# 3_Phase_Controller_V0_1.net
KiCad netlist of a schematic drawn in EAGLE
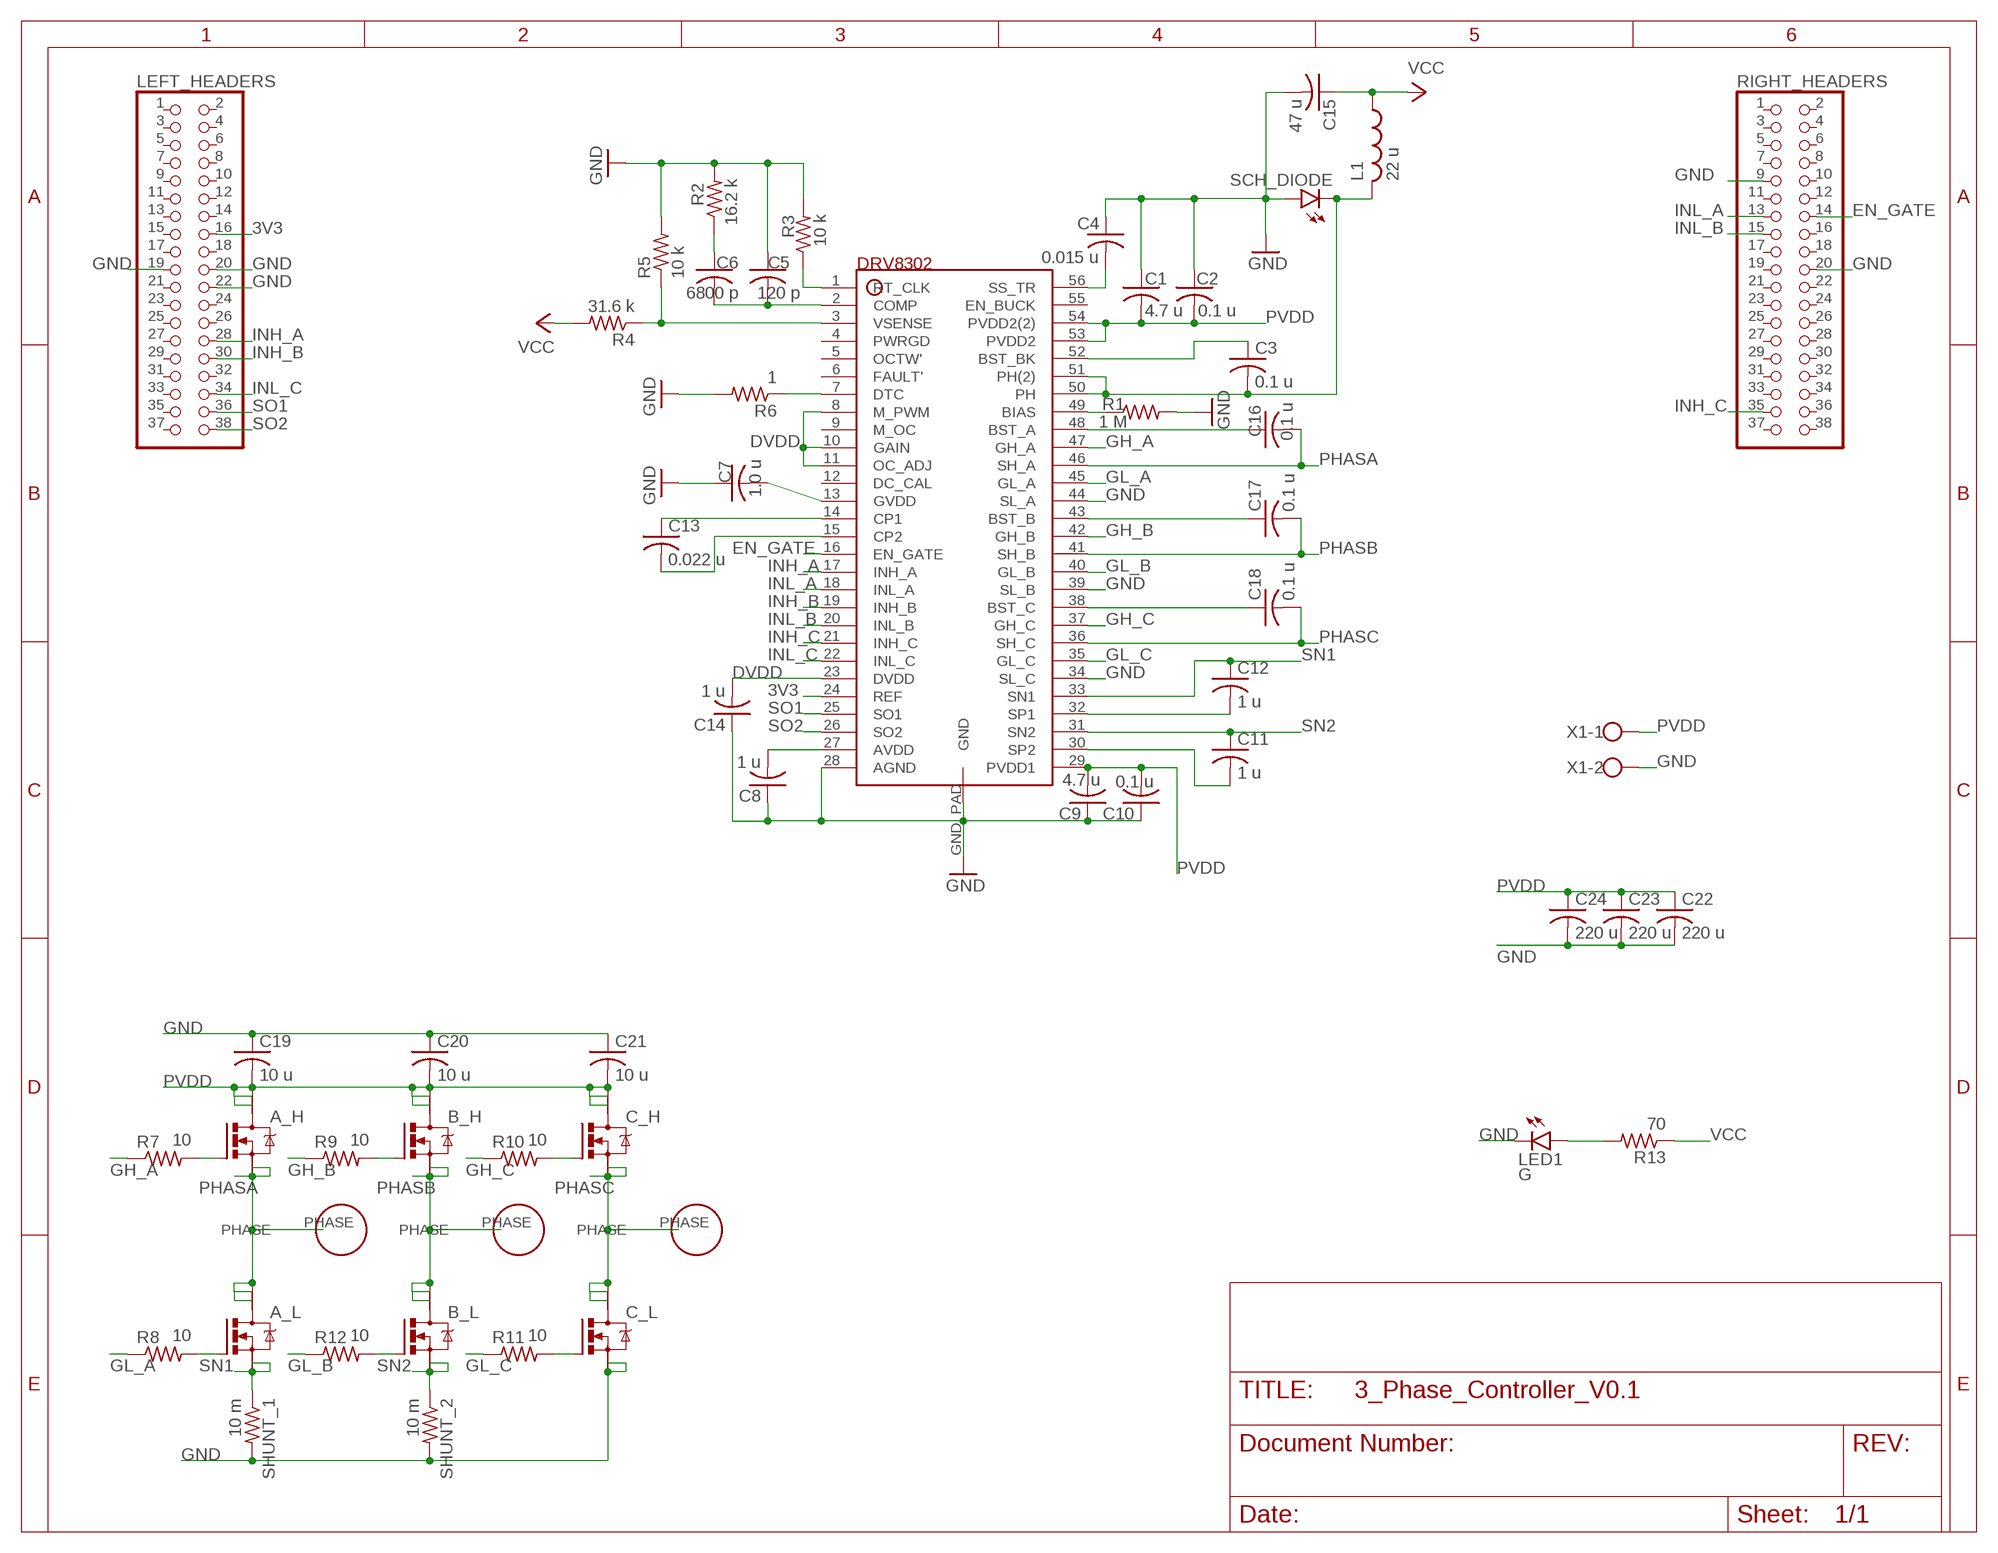
[diagram p0: schematic, sheet 1]

(export (version "E")
  (design (tool "Eeschema 10.0.6"))
  (components
    (comp (ref "A")
      (value "PHASE_HOLE")
      (footprint "eagle-import:HOLE")
      (libsource (lib "eagle-import") (part "PHASE_HOLE"))
    )
    (comp (ref "A_H")
      (value "N-MOSFET-SO8S")
      (footprint "eagle-import:SO-08")
      (libsource (lib "eagle-import") (part "N-MOSFET-SO8S"))
    )
    (comp (ref "A_L")
      (value "N-MOSFET-SO8S")
      (footprint "eagle-import:SO-08")
      (libsource (lib "eagle-import") (part "N-MOSFET-SO8S"))
    )
    (comp (ref "B")
      (value "PHASE_HOLE")
      (footprint "eagle-import:HOLE")
      (libsource (lib "eagle-import") (part "PHASE_HOLE"))
    )
    (comp (ref "B_H")
      (value "N-MOSFET-SO8S")
      (footprint "eagle-import:SO-08")
      (libsource (lib "eagle-import") (part "N-MOSFET-SO8S"))
    )
    (comp (ref "B_L")
      (value "N-MOSFET-SO8S")
      (footprint "eagle-import:SO-08")
      (libsource (lib "eagle-import") (part "N-MOSFET-SO8S"))
    )
    (comp (ref "C")
      (value "PHASE_HOLE")
      (footprint "eagle-import:HOLE")
      (libsource (lib "eagle-import") (part "PHASE_HOLE"))
    )
    (comp (ref "C1")
      (value "4.7 u")
      (footprint "eagle-import:C0805")
      (libsource (lib "eagle-import") (part "C-USC0805"))
    )
    (comp (ref "C2")
      (value "0.1 u")
      (footprint "eagle-import:C0805")
      (libsource (lib "eagle-import") (part "C-USC0805"))
    )
    (comp (ref "C3")
      (value "0.1 u")
      (footprint "eagle-import:C0805")
      (libsource (lib "eagle-import") (part "C-USC0805"))
    )
    (comp (ref "C4")
      (value "0.015 u")
      (footprint "eagle-import:C0805")
      (libsource (lib "eagle-import") (part "C-USC0805"))
    )
    (comp (ref "C5")
      (value "120 p")
      (footprint "eagle-import:C0805")
      (libsource (lib "eagle-import") (part "C-USC0805"))
    )
    (comp (ref "C6")
      (value "6800 p")
      (footprint "eagle-import:C0805")
      (libsource (lib "eagle-import") (part "C-USC0805"))
    )
    (comp (ref "C7")
      (value "1.0 u")
      (footprint "eagle-import:C0805")
      (libsource (lib "eagle-import") (part "C-USC0805"))
    )
    (comp (ref "C8")
      (value "1 u")
      (footprint "eagle-import:C0805")
      (libsource (lib "eagle-import") (part "C-USC0805"))
    )
    (comp (ref "C9")
      (value "4.7 u")
      (footprint "eagle-import:C0805")
      (libsource (lib "eagle-import") (part "C-USC0805"))
    )
    (comp (ref "C10")
      (value "0.1 u")
      (footprint "eagle-import:C0805")
      (libsource (lib "eagle-import") (part "C-USC0805"))
    )
    (comp (ref "C11")
      (value "1 u")
      (footprint "eagle-import:C0805")
      (libsource (lib "eagle-import") (part "C-USC0805"))
    )
    (comp (ref "C12")
      (value "1 u")
      (footprint "eagle-import:C0805")
      (libsource (lib "eagle-import") (part "C-USC0805"))
    )
    (comp (ref "C13")
      (value "0.022 u")
      (footprint "eagle-import:C0805")
      (libsource (lib "eagle-import") (part "C-USC0805"))
    )
    (comp (ref "C14")
      (value "1 u")
      (footprint "eagle-import:C0805")
      (libsource (lib "eagle-import") (part "C-USC0805"))
    )
    (comp (ref "C15")
      (value "47 u")
      (footprint "eagle-import:C025-024X044")
      (libsource (lib "eagle-import") (part "C-US025-024X044"))
    )
    (comp (ref "C16")
      (value "0.1 u")
      (footprint "eagle-import:C0805")
      (libsource (lib "eagle-import") (part "C-USC0805"))
    )
    (comp (ref "C17")
      (value "0.1 u")
      (footprint "eagle-import:C0805")
      (libsource (lib "eagle-import") (part "C-USC0805"))
    )
    (comp (ref "C18")
      (value "0.1 u")
      (footprint "eagle-import:C0805")
      (libsource (lib "eagle-import") (part "C-USC0805"))
    )
    (comp (ref "C19")
      (value "10 u")
      (footprint "eagle-import:C1206")
      (libsource (lib "eagle-import") (part "C-USC1206"))
    )
    (comp (ref "C20")
      (value "10 u")
      (footprint "eagle-import:C1206")
      (libsource (lib "eagle-import") (part "C-USC1206"))
    )
    (comp (ref "C21")
      (value "10 u")
      (footprint "eagle-import:C1206")
      (libsource (lib "eagle-import") (part "C-USC1206"))
    )
    (comp (ref "C22")
      (value "220 u")
      (footprint "eagle-import:C050-045X075")
      (libsource (lib "eagle-import") (part "C-US050-045X075"))
    )
    (comp (ref "C23")
      (value "220 u")
      (footprint "eagle-import:C050-045X075")
      (libsource (lib "eagle-import") (part "C-US050-045X075"))
    )
    (comp (ref "C24")
      (value "220 u")
      (footprint "eagle-import:C050-045X075")
      (libsource (lib "eagle-import") (part "C-US050-045X075"))
    )
    (comp (ref "C_H")
      (value "N-MOSFET-SO8S")
      (footprint "eagle-import:SO-08")
      (libsource (lib "eagle-import") (part "N-MOSFET-SO8S"))
    )
    (comp (ref "C_L")
      (value "N-MOSFET-SO8S")
      (footprint "eagle-import:SO-08")
      (libsource (lib "eagle-import") (part "N-MOSFET-SO8S"))
    )
    (comp (ref "DRV8302")
      (value "DRV8302HTSSOP_56")
      (footprint "eagle-import:HTSSOP56DFD")
      (libsource (lib "eagle-import") (part "DRV8302HTSSOP_56"))
    )
    (comp (ref "L1")
      (value "22 u")
      (footprint "eagle-import:L3225M")
      (libsource (lib "eagle-import") (part "L-USL3225M"))
    )
    (comp (ref "LED1")
      (value "G")
      (footprint "eagle-import:SML0805")
      (libsource (lib "eagle-import") (part "LEDSML0805"))
    )
    (comp (ref "LEFT_HEADERS")
      (value "F_PINH 2X19")
      (footprint "eagle-import:2X19")
      (libsource (lib "eagle-import") (part "PINHD-2X19"))
    )
    (comp (ref "R1")
      (value "1 M")
      (footprint "eagle-import:R0805")
      (libsource (lib "eagle-import") (part "R-US_R0805"))
    )
    (comp (ref "R2")
      (value "16.2 k")
      (footprint "eagle-import:R0805")
      (libsource (lib "eagle-import") (part "R-US_R0805"))
    )
    (comp (ref "R3")
      (value "10 k")
      (footprint "eagle-import:R0805")
      (libsource (lib "eagle-import") (part "R-US_R0805"))
    )
    (comp (ref "R4")
      (value "31.6 k")
      (footprint "eagle-import:R0805")
      (libsource (lib "eagle-import") (part "R-US_R0805"))
    )
    (comp (ref "R5")
      (value "10 k")
      (footprint "eagle-import:R0805")
      (libsource (lib "eagle-import") (part "R-US_R0805"))
    )
    (comp (ref "R6")
      (value "1")
      (footprint "eagle-import:R0805")
      (libsource (lib "eagle-import") (part "R-US_R0805"))
    )
    (comp (ref "R7")
      (value "10")
      (footprint "eagle-import:R0805")
      (libsource (lib "eagle-import") (part "R-US_R0805"))
    )
    (comp (ref "R8")
      (value "10")
      (footprint "eagle-import:R0805")
      (libsource (lib "eagle-import") (part "R-US_R0805"))
    )
    (comp (ref "R9")
      (value "10")
      (footprint "eagle-import:R0805")
      (libsource (lib "eagle-import") (part "R-US_R0805"))
    )
    (comp (ref "R10")
      (value "10")
      (footprint "eagle-import:R0805")
      (libsource (lib "eagle-import") (part "R-US_R0805"))
    )
    (comp (ref "R11")
      (value "10")
      (footprint "eagle-import:R0805")
      (libsource (lib "eagle-import") (part "R-US_R0805"))
    )
    (comp (ref "R12")
      (value "10")
      (footprint "eagle-import:R0805")
      (libsource (lib "eagle-import") (part "R-US_R0805"))
    )
    (comp (ref "R13")
      (value "70")
      (footprint "eagle-import:R0805")
      (libsource (lib "eagle-import") (part "R-US_R0805"))
    )
    (comp (ref "RIGHT_HEADERS")
      (value "F_PINH 2X19")
      (footprint "eagle-import:2X19")
      (libsource (lib "eagle-import") (part "PINHD-2X19"))
    )
    (comp (ref "SCH_DIODE")
      (value "LEDCHIP-LED0805")
      (footprint "eagle-import:CHIP-LED0805")
      (libsource (lib "eagle-import") (part "LEDCHIP-LED0805"))
    )
    (comp (ref "SHUNT_1")
      (value "10 m")
      (footprint "eagle-import:R2512")
      (libsource (lib "eagle-import") (part "R-US_R2512"))
    )
    (comp (ref "SHUNT_2")
      (value "10 m")
      (footprint "eagle-import:R2512")
      (libsource (lib "eagle-import") (part "R-US_R2512"))
    )
    (comp (ref "X1")
      (value "W237-102")
      (footprint "eagle-import:W237-102")
      (fields (field (name "MPN") "237-102"))
      (libsource (lib "eagle-import") (part "W237-102"))
    )
  )
  (nets
    (net (code "1") (name "/3V3") (class "Default")
      (node (ref "DRV8302") (pin "24") (pinfunction "REF_24") (pintype "bidirectional"))
      (node (ref "LEFT_HEADERS") (pin "16") (pinfunction "16_16") (pintype "passive"))
    )
    (net (code "2") (name "/DVDD") (class "Default")
      (node (ref "C14") (pin "2") (pinfunction "2_2") (pintype "passive"))
      (node (ref "DRV8302") (pin "10") (pinfunction "GAIN_10") (pintype "bidirectional"))
      (node (ref "DRV8302") (pin "11") (pinfunction "OC_ADJ_11") (pintype "bidirectional"))
      (node (ref "DRV8302") (pin "23") (pinfunction "DVDD_23") (pintype "bidirectional"))
      (node (ref "DRV8302") (pin "8") (pinfunction "M_PWM_8") (pintype "bidirectional"))
    )
    (net (code "3") (name "/EN_GATE") (class "Default")
      (node (ref "DRV8302") (pin "16") (pinfunction "EN_GATE_16") (pintype "bidirectional"))
      (node (ref "RIGHT_HEADERS") (pin "14") (pinfunction "14_14") (pintype "passive"))
    )
    (net (code "4") (name "/GH_A") (class "Default")
      (node (ref "DRV8302") (pin "47") (pinfunction "GH_A_47") (pintype "bidirectional"))
      (node (ref "R7") (pin "1") (pinfunction "1_1") (pintype "passive"))
    )
    (net (code "5") (name "/GH_B") (class "Default")
      (node (ref "DRV8302") (pin "42") (pinfunction "GH_B_42") (pintype "bidirectional"))
      (node (ref "R9") (pin "1") (pinfunction "1_1") (pintype "passive"))
    )
    (net (code "6") (name "/GH_C") (class "Default")
      (node (ref "DRV8302") (pin "37") (pinfunction "GH_C_37") (pintype "bidirectional"))
      (node (ref "R10") (pin "1") (pinfunction "1_1") (pintype "passive"))
    )
    (net (code "7") (name "/GL_A") (class "Default")
      (node (ref "DRV8302") (pin "45") (pinfunction "GL_A_45") (pintype "bidirectional"))
      (node (ref "R8") (pin "1") (pinfunction "1_1") (pintype "passive"))
    )
    (net (code "8") (name "/GL_B") (class "Default")
      (node (ref "DRV8302") (pin "40") (pinfunction "GL_B_40") (pintype "bidirectional"))
      (node (ref "R12") (pin "1") (pinfunction "1_1") (pintype "passive"))
    )
    (net (code "9") (name "/GL_C") (class "Default")
      (node (ref "DRV8302") (pin "35") (pinfunction "GL_C_35") (pintype "bidirectional"))
      (node (ref "R11") (pin "1") (pinfunction "1_1") (pintype "passive"))
    )
    (net (code "10") (name "/INH_A") (class "Default")
      (node (ref "DRV8302") (pin "17") (pinfunction "INH_A_17") (pintype "bidirectional"))
      (node (ref "LEFT_HEADERS") (pin "28") (pinfunction "28_28") (pintype "passive"))
    )
    (net (code "11") (name "/INH_B") (class "Default")
      (node (ref "DRV8302") (pin "19") (pinfunction "INH_B_19") (pintype "bidirectional"))
      (node (ref "LEFT_HEADERS") (pin "30") (pinfunction "30_30") (pintype "passive"))
    )
    (net (code "12") (name "/INH_C") (class "Default")
      (node (ref "DRV8302") (pin "21") (pinfunction "INH_C_21") (pintype "bidirectional"))
      (node (ref "RIGHT_HEADERS") (pin "35") (pinfunction "35_35") (pintype "passive"))
    )
    (net (code "13") (name "/INL_A") (class "Default")
      (node (ref "DRV8302") (pin "18") (pinfunction "INL_A_18") (pintype "bidirectional"))
      (node (ref "RIGHT_HEADERS") (pin "13") (pinfunction "13_13") (pintype "passive"))
    )
    (net (code "14") (name "/INL_B") (class "Default")
      (node (ref "DRV8302") (pin "20") (pinfunction "INL_B_20") (pintype "bidirectional"))
      (node (ref "RIGHT_HEADERS") (pin "15") (pinfunction "15_15") (pintype "passive"))
    )
    (net (code "15") (name "/INL_C") (class "Default")
      (node (ref "DRV8302") (pin "22") (pinfunction "INL_C_22") (pintype "bidirectional"))
      (node (ref "LEFT_HEADERS") (pin "34") (pinfunction "34_34") (pintype "passive"))
    )
    (net (code "16") (name "/PHASA") (class "Default")
      (node (ref "A") (pin "PHASE") (pinfunction "PHASE_PHASE") (pintype "bidirectional"))
      (node (ref "A_H") (pin "1") (pinfunction "S_1") (pintype "passive"))
      (node (ref "A_H") (pin "2") (pinfunction "S_2") (pintype "passive"))
      (node (ref "A_L") (pin "5") (pinfunction "D_5") (pintype "passive"))
      (node (ref "A_L") (pin "6") (pinfunction "D_6") (pintype "passive"))
      (node (ref "A_L") (pin "7") (pinfunction "D_7") (pintype "passive"))
      (node (ref "C16") (pin "2") (pinfunction "2_2") (pintype "passive"))
      (node (ref "DRV8302") (pin "46") (pinfunction "SH_A_46") (pintype "bidirectional"))
    )
    (net (code "17") (name "/PHASB") (class "Default")
      (node (ref "B") (pin "PHASE") (pinfunction "PHASE_PHASE") (pintype "bidirectional"))
      (node (ref "B_H") (pin "1") (pinfunction "S_1") (pintype "passive"))
      (node (ref "B_H") (pin "2") (pinfunction "S_2") (pintype "passive"))
      (node (ref "B_L") (pin "5") (pinfunction "D_5") (pintype "passive"))
      (node (ref "B_L") (pin "6") (pinfunction "D_6") (pintype "passive"))
      (node (ref "B_L") (pin "7") (pinfunction "D_7") (pintype "passive"))
      (node (ref "C17") (pin "2") (pinfunction "2_2") (pintype "passive"))
      (node (ref "DRV8302") (pin "41") (pinfunction "SH_B_41") (pintype "bidirectional"))
    )
    (net (code "18") (name "/PHASC") (class "Default")
      (node (ref "C") (pin "PHASE") (pinfunction "PHASE_PHASE") (pintype "bidirectional"))
      (node (ref "C18") (pin "2") (pinfunction "2_2") (pintype "passive"))
      (node (ref "C_H") (pin "1") (pinfunction "S_1") (pintype "passive"))
      (node (ref "C_H") (pin "2") (pinfunction "S_2") (pintype "passive"))
      (node (ref "C_L") (pin "5") (pinfunction "D_5") (pintype "passive"))
      (node (ref "C_L") (pin "6") (pinfunction "D_6") (pintype "passive"))
      (node (ref "C_L") (pin "7") (pinfunction "D_7") (pintype "passive"))
      (node (ref "DRV8302") (pin "36") (pinfunction "SH_C_36") (pintype "bidirectional"))
    )
    (net (code "19") (name "/PVDD") (class "Default")
      (node (ref "A_H") (pin "5") (pinfunction "D_5") (pintype "passive"))
      (node (ref "A_H") (pin "6") (pinfunction "D_6") (pintype "passive"))
      (node (ref "A_H") (pin "7") (pinfunction "D_7") (pintype "passive"))
      (node (ref "B_H") (pin "5") (pinfunction "D_5") (pintype "passive"))
      (node (ref "B_H") (pin "6") (pinfunction "D_6") (pintype "passive"))
      (node (ref "B_H") (pin "7") (pinfunction "D_7") (pintype "passive"))
      (node (ref "C1") (pin "2") (pinfunction "2_2") (pintype "passive"))
      (node (ref "C10") (pin "2") (pinfunction "2_2") (pintype "passive"))
      (node (ref "C19") (pin "2") (pinfunction "2_2") (pintype "passive"))
      (node (ref "C2") (pin "2") (pinfunction "2_2") (pintype "passive"))
      (node (ref "C20") (pin "2") (pinfunction "2_2") (pintype "passive"))
      (node (ref "C21") (pin "2") (pinfunction "2_2") (pintype "passive"))
      (node (ref "C22") (pin "1") (pinfunction "1_1") (pintype "passive"))
      (node (ref "C23") (pin "1") (pinfunction "1_1") (pintype "passive"))
      (node (ref "C24") (pin "1") (pinfunction "1_1") (pintype "passive"))
      (node (ref "C9") (pin "2") (pinfunction "2_2") (pintype "passive"))
      (node (ref "C_H") (pin "5") (pinfunction "D_5") (pintype "passive"))
      (node (ref "C_H") (pin "6") (pinfunction "D_6") (pintype "passive"))
      (node (ref "C_H") (pin "7") (pinfunction "D_7") (pintype "passive"))
      (node (ref "DRV8302") (pin "29") (pinfunction "PVDD1_29") (pintype "bidirectional"))
      (node (ref "DRV8302") (pin "53") (pinfunction "PVDD2_53") (pintype "bidirectional"))
      (node (ref "DRV8302") (pin "54") (pinfunction "PVDD2(2)_54") (pintype "bidirectional"))
      (node (ref "X1") (pin "1") (pinfunction "KL_1") (pintype "passive"))
    )
    (net (code "20") (name "/SN1") (class "Default")
      (node (ref "A_L") (pin "1") (pinfunction "S_1") (pintype "passive"))
      (node (ref "A_L") (pin "2") (pinfunction "S_2") (pintype "passive"))
      (node (ref "C12") (pin "1") (pinfunction "1_1") (pintype "passive"))
      (node (ref "DRV8302") (pin "33") (pinfunction "SN1_33") (pintype "bidirectional"))
      (node (ref "SHUNT_1") (pin "1") (pinfunction "1_1") (pintype "passive"))
    )
    (net (code "21") (name "/SN2") (class "Default")
      (node (ref "B_L") (pin "1") (pinfunction "S_1") (pintype "passive"))
      (node (ref "B_L") (pin "2") (pinfunction "S_2") (pintype "passive"))
      (node (ref "C11") (pin "1") (pinfunction "1_1") (pintype "passive"))
      (node (ref "DRV8302") (pin "31") (pinfunction "SN2_31") (pintype "bidirectional"))
      (node (ref "SHUNT_2") (pin "1") (pinfunction "1_1") (pintype "passive"))
    )
    (net (code "22") (name "/SO1") (class "Default")
      (node (ref "DRV8302") (pin "25") (pinfunction "SO1_25") (pintype "bidirectional"))
      (node (ref "LEFT_HEADERS") (pin "36") (pinfunction "36_36") (pintype "passive"))
    )
    (net (code "23") (name "/SO2") (class "Default")
      (node (ref "DRV8302") (pin "26") (pinfunction "SO2_26") (pintype "bidirectional"))
      (node (ref "LEFT_HEADERS") (pin "38") (pinfunction "38_38") (pintype "passive"))
    )
    (net (code "24") (name "GND") (class "Default")
      (node (ref "C1") (pin "1") (pinfunction "1_1") (pintype "passive"))
      (node (ref "C10") (pin "1") (pinfunction "1_1") (pintype "passive"))
      (node (ref "C14") (pin "1") (pinfunction "1_1") (pintype "passive"))
      (node (ref "C15") (pin "2") (pinfunction "2_2") (pintype "passive"))
      (node (ref "C19") (pin "1") (pinfunction "1_1") (pintype "passive"))
      (node (ref "C2") (pin "1") (pinfunction "1_1") (pintype "passive"))
      (node (ref "C20") (pin "1") (pinfunction "1_1") (pintype "passive"))
      (node (ref "C21") (pin "1") (pinfunction "1_1") (pintype "passive"))
      (node (ref "C22") (pin "2") (pinfunction "2_2") (pintype "passive"))
      (node (ref "C23") (pin "2") (pinfunction "2_2") (pintype "passive"))
      (node (ref "C24") (pin "2") (pinfunction "2_2") (pintype "passive"))
      (node (ref "C4") (pin "1") (pinfunction "1_1") (pintype "passive"))
      (node (ref "C5") (pin "1") (pinfunction "1_1") (pintype "passive"))
      (node (ref "C7") (pin "1") (pinfunction "1_1") (pintype "passive"))
      (node (ref "C8") (pin "1") (pinfunction "1_1") (pintype "passive"))
      (node (ref "C9") (pin "1") (pinfunction "1_1") (pintype "passive"))
      (node (ref "C_L") (pin "1") (pinfunction "S_1") (pintype "passive"))
      (node (ref "C_L") (pin "2") (pinfunction "S_2") (pintype "passive"))
      (node (ref "DRV8302") (pin "28") (pinfunction "AGND_28") (pintype "bidirectional"))
      (node (ref "DRV8302") (pin "34") (pinfunction "SL_C_34") (pintype "bidirectional"))
      (node (ref "DRV8302") (pin "39") (pinfunction "SL_B_39") (pintype "bidirectional"))
      (node (ref "DRV8302") (pin "44") (pinfunction "SL_A_44") (pintype "bidirectional"))
      (node (ref "DRV8302") (pin "GND_PAD") (pinfunction "GND_GND_PAD") (pintype "bidirectional"))
      (node (ref "LED1") (pin "C") (pinfunction "C_C") (pintype "passive"))
      (node (ref "LEFT_HEADERS") (pin "19") (pinfunction "19_19") (pintype "passive"))
      (node (ref "LEFT_HEADERS") (pin "20") (pinfunction "20_20") (pintype "passive"))
      (node (ref "LEFT_HEADERS") (pin "22") (pinfunction "22_22") (pintype "passive"))
      (node (ref "R1") (pin "2") (pinfunction "2_2") (pintype "passive"))
      (node (ref "R2") (pin "2") (pinfunction "2_2") (pintype "passive"))
      (node (ref "R3") (pin "2") (pinfunction "2_2") (pintype "passive"))
      (node (ref "R5") (pin "2") (pinfunction "2_2") (pintype "passive"))
      (node (ref "R6") (pin "2") (pinfunction "2_2") (pintype "passive"))
      (node (ref "RIGHT_HEADERS") (pin "20") (pinfunction "20_20") (pintype "passive"))
      (node (ref "RIGHT_HEADERS") (pin "9") (pinfunction "9_9") (pintype "passive"))
      (node (ref "SCH_DIODE") (pin "A") (pinfunction "A_A") (pintype "passive"))
      (node (ref "SHUNT_1") (pin "2") (pinfunction "2_2") (pintype "passive"))
      (node (ref "SHUNT_2") (pin "2") (pinfunction "2_2") (pintype "passive"))
      (node (ref "X1") (pin "2") (pinfunction "KL_2") (pintype "passive"))
    )
    (net (code "25") (name "Net-(A_H-G)") (class "Default")
      (node (ref "A_H") (pin "4") (pinfunction "G_4") (pintype "passive"))
      (node (ref "R7") (pin "2") (pinfunction "2_2") (pintype "passive"))
    )
    (net (code "26") (name "Net-(A_L-G)") (class "Default")
      (node (ref "A_L") (pin "4") (pinfunction "G_4") (pintype "passive"))
      (node (ref "R8") (pin "2") (pinfunction "2_2") (pintype "passive"))
    )
    (net (code "27") (name "Net-(B_H-G)") (class "Default")
      (node (ref "B_H") (pin "4") (pinfunction "G_4") (pintype "passive"))
      (node (ref "R9") (pin "2") (pinfunction "2_2") (pintype "passive"))
    )
    (net (code "28") (name "Net-(B_L-G)") (class "Default")
      (node (ref "B_L") (pin "4") (pinfunction "G_4") (pintype "passive"))
      (node (ref "R12") (pin "2") (pinfunction "2_2") (pintype "passive"))
    )
    (net (code "29") (name "Net-(C6-Pad1)") (class "Default")
      (node (ref "C6") (pin "1") (pinfunction "1_1") (pintype "passive"))
      (node (ref "R2") (pin "1") (pinfunction "1_1") (pintype "passive"))
    )
    (net (code "30") (name "Net-(C_H-G)") (class "Default")
      (node (ref "C_H") (pin "4") (pinfunction "G_4") (pintype "passive"))
      (node (ref "R10") (pin "2") (pinfunction "2_2") (pintype "passive"))
    )
    (net (code "31") (name "Net-(C_L-G)") (class "Default")
      (node (ref "C_L") (pin "4") (pinfunction "G_4") (pintype "passive"))
      (node (ref "R11") (pin "2") (pinfunction "2_2") (pintype "passive"))
    )
    (net (code "32") (name "Net-(DRV8302-AVDD)") (class "Default")
      (node (ref "C8") (pin "2") (pinfunction "2_2") (pintype "passive"))
      (node (ref "DRV8302") (pin "27") (pinfunction "AVDD_27") (pintype "bidirectional"))
    )
    (net (code "33") (name "Net-(DRV8302-BIAS)") (class "Default")
      (node (ref "DRV8302") (pin "49") (pinfunction "BIAS_49") (pintype "bidirectional"))
      (node (ref "R1") (pin "1") (pinfunction "1_1") (pintype "passive"))
    )
    (net (code "34") (name "Net-(DRV8302-BST_A)") (class "Default")
      (node (ref "C16") (pin "1") (pinfunction "1_1") (pintype "passive"))
      (node (ref "DRV8302") (pin "48") (pinfunction "BST_A_48") (pintype "bidirectional"))
    )
    (net (code "35") (name "Net-(DRV8302-BST_B)") (class "Default")
      (node (ref "C17") (pin "1") (pinfunction "1_1") (pintype "passive"))
      (node (ref "DRV8302") (pin "43") (pinfunction "BST_B_43") (pintype "bidirectional"))
    )
    (net (code "36") (name "Net-(DRV8302-BST_BK)") (class "Default")
      (node (ref "C3") (pin "1") (pinfunction "1_1") (pintype "passive"))
      (node (ref "DRV8302") (pin "52") (pinfunction "BST_BK_52") (pintype "bidirectional"))
    )
    (net (code "37") (name "Net-(DRV8302-BST_C)") (class "Default")
      (node (ref "C18") (pin "1") (pinfunction "1_1") (pintype "passive"))
      (node (ref "DRV8302") (pin "38") (pinfunction "BST_C_38") (pintype "bidirectional"))
    )
    (net (code "38") (name "Net-(DRV8302-COMP)") (class "Default")
      (node (ref "C5") (pin "2") (pinfunction "2_2") (pintype "passive"))
      (node (ref "C6") (pin "2") (pinfunction "2_2") (pintype "passive"))
      (node (ref "DRV8302") (pin "2") (pinfunction "COMP_2") (pintype "bidirectional"))
    )
    (net (code "39") (name "Net-(DRV8302-CP1)") (class "Default")
      (node (ref "C13") (pin "1") (pinfunction "1_1") (pintype "passive"))
      (node (ref "DRV8302") (pin "14") (pinfunction "CP1_14") (pintype "bidirectional"))
    )
    (net (code "40") (name "Net-(DRV8302-CP2)") (class "Default")
      (node (ref "C13") (pin "2") (pinfunction "2_2") (pintype "passive"))
      (node (ref "DRV8302") (pin "15") (pinfunction "CP2_15") (pintype "bidirectional"))
    )
    (net (code "41") (name "Net-(DRV8302-DTC)") (class "Default")
      (node (ref "DRV8302") (pin "7") (pinfunction "DTC_7") (pintype "bidirectional"))
      (node (ref "R6") (pin "1") (pinfunction "1_1") (pintype "passive"))
    )
    (net (code "42") (name "Net-(DRV8302-GVDD)") (class "Default")
      (node (ref "C7") (pin "2") (pinfunction "2_2") (pintype "passive"))
      (node (ref "DRV8302") (pin "13") (pinfunction "GVDD_13") (pintype "bidirectional"))
    )
    (net (code "43") (name "Net-(DRV8302-PH(2))") (class "Default")
      (node (ref "C3") (pin "2") (pinfunction "2_2") (pintype "passive"))
      (node (ref "DRV8302") (pin "50") (pinfunction "PH_50") (pintype "bidirectional"))
      (node (ref "DRV8302") (pin "51") (pinfunction "PH(2)_51") (pintype "bidirectional"))
      (node (ref "L1") (pin "2") (pinfunction "2_2") (pintype "passive"))
      (node (ref "SCH_DIODE") (pin "C") (pinfunction "C_C") (pintype "passive"))
    )
    (net (code "44") (name "Net-(DRV8302-RT_CLK)") (class "Default")
      (node (ref "DRV8302") (pin "1") (pinfunction "RT_CLK_1") (pintype "bidirectional"))
      (node (ref "R3") (pin "1") (pinfunction "1_1") (pintype "passive"))
    )
    (net (code "45") (name "Net-(DRV8302-SP1)") (class "Default")
      (node (ref "C12") (pin "2") (pinfunction "2_2") (pintype "passive"))
      (node (ref "DRV8302") (pin "32") (pinfunction "SP1_32") (pintype "bidirectional"))
    )
    (net (code "46") (name "Net-(DRV8302-SP2)") (class "Default")
      (node (ref "C11") (pin "2") (pinfunction "2_2") (pintype "passive"))
      (node (ref "DRV8302") (pin "30") (pinfunction "SP2_30") (pintype "bidirectional"))
    )
    (net (code "47") (name "Net-(DRV8302-SS_TR)") (class "Default")
      (node (ref "C4") (pin "2") (pinfunction "2_2") (pintype "passive"))
      (node (ref "DRV8302") (pin "56") (pinfunction "SS_TR_56") (pintype "bidirectional"))
    )
    (net (code "48") (name "Net-(DRV8302-VSENSE)") (class "Default")
      (node (ref "DRV8302") (pin "3") (pinfunction "VSENSE_3") (pintype "bidirectional"))
      (node (ref "R4") (pin "1") (pinfunction "1_1") (pintype "passive"))
      (node (ref "R5") (pin "1") (pinfunction "1_1") (pintype "passive"))
    )
    (net (code "49") (name "Net-(LED1-PadA)") (class "Default")
      (node (ref "LED1") (pin "A") (pinfunction "A_A") (pintype "passive"))
      (node (ref "R13") (pin "2") (pinfunction "2_2") (pintype "passive"))
    )
    (net (code "50") (name "VCC") (class "Default")
      (node (ref "C15") (pin "1") (pinfunction "1_1") (pintype "passive"))
      (node (ref "L1") (pin "1") (pinfunction "1_1") (pintype "passive"))
      (node (ref "R13") (pin "1") (pinfunction "1_1") (pintype "passive"))
      (node (ref "R4") (pin "2") (pinfunction "2_2") (pintype "passive"))
    )
    (net (code "51") (name "unconnected-(A_H-D-Pad8)") (class "Default")
      (node (ref "A_H") (pin "8") (pinfunction "D_8") (pintype "passive"))
    )
    (net (code "52") (name "unconnected-(A_H-S-Pad3)") (class "Default")
      (node (ref "A_H") (pin "3") (pinfunction "S_3") (pintype "passive"))
    )
    (net (code "53") (name "unconnected-(A_L-D-Pad8)") (class "Default")
      (node (ref "A_L") (pin "8") (pinfunction "D_8") (pintype "passive"))
    )
    (net (code "54") (name "unconnected-(A_L-S-Pad3)") (class "Default")
      (node (ref "A_L") (pin "3") (pinfunction "S_3") (pintype "passive"))
    )
    (net (code "55") (name "unconnected-(B_H-D-Pad8)") (class "Default")
      (node (ref "B_H") (pin "8") (pinfunction "D_8") (pintype "passive"))
    )
    (net (code "56") (name "unconnected-(B_H-S-Pad3)") (class "Default")
      (node (ref "B_H") (pin "3") (pinfunction "S_3") (pintype "passive"))
    )
    (net (code "57") (name "unconnected-(B_L-D-Pad8)") (class "Default")
      (node (ref "B_L") (pin "8") (pinfunction "D_8") (pintype "passive"))
    )
    (net (code "58") (name "unconnected-(B_L-S-Pad3)") (class "Default")
      (node (ref "B_L") (pin "3") (pinfunction "S_3") (pintype "passive"))
    )
    (net (code "59") (name "unconnected-(C_H-D-Pad8)") (class "Default")
      (node (ref "C_H") (pin "8") (pinfunction "D_8") (pintype "passive"))
    )
    (net (code "60") (name "unconnected-(C_H-S-Pad3)") (class "Default")
      (node (ref "C_H") (pin "3") (pinfunction "S_3") (pintype "passive"))
    )
    (net (code "61") (name "unconnected-(C_L-D-Pad8)") (class "Default")
      (node (ref "C_L") (pin "8") (pinfunction "D_8") (pintype "passive"))
    )
    (net (code "62") (name "unconnected-(C_L-S-Pad3)") (class "Default")
      (node (ref "C_L") (pin "3") (pinfunction "S_3") (pintype "passive"))
    )
    (net (code "63") (name "unconnected-(DRV8302-DC_CAL-Pad12)") (class "Default")
      (node (ref "DRV8302") (pin "12") (pinfunction "DC_CAL_12") (pintype "bidirectional"))
    )
    (net (code "64") (name "unconnected-(DRV8302-EN_BUCK-Pad55)") (class "Default")
      (node (ref "DRV8302") (pin "55") (pinfunction "EN_BUCK_55") (pintype "bidirectional"))
    )
    (net (code "65") (name "unconnected-(DRV8302-FAULT'-Pad6)") (class "Default")
      (node (ref "DRV8302") (pin "6") (pinfunction "FAULT'_6") (pintype "bidirectional"))
    )
    (net (code "66") (name "unconnected-(DRV8302-M_OC-Pad9)") (class "Default")
      (node (ref "DRV8302") (pin "9") (pinfunction "M_OC_9") (pintype "bidirectional"))
    )
    (net (code "67") (name "unconnected-(DRV8302-OCTW'-Pad5)") (class "Default")
      (node (ref "DRV8302") (pin "5") (pinfunction "OCTW'_5") (pintype "bidirectional"))
    )
    (net (code "68") (name "unconnected-(DRV8302-PWRGD-Pad4)") (class "Default")
      (node (ref "DRV8302") (pin "4") (pinfunction "PWRGD_4") (pintype "bidirectional"))
    )
    (net (code "69") (name "unconnected-(LEFT_HEADERS-Pad1)") (class "Default")
      (node (ref "LEFT_HEADERS") (pin "1") (pinfunction "1_1") (pintype "passive"))
    )
    (net (code "70") (name "unconnected-(LEFT_HEADERS-Pad2)") (class "Default")
      (node (ref "LEFT_HEADERS") (pin "2") (pinfunction "2_2") (pintype "passive"))
    )
    (net (code "71") (name "unconnected-(LEFT_HEADERS-Pad3)") (class "Default")
      (node (ref "LEFT_HEADERS") (pin "3") (pinfunction "3_3") (pintype "passive"))
    )
    (net (code "72") (name "unconnected-(LEFT_HEADERS-Pad4)") (class "Default")
      (node (ref "LEFT_HEADERS") (pin "4") (pinfunction "4_4") (pintype "passive"))
    )
    (net (code "73") (name "unconnected-(LEFT_HEADERS-Pad5)") (class "Default")
      (node (ref "LEFT_HEADERS") (pin "5") (pinfunction "5_5") (pintype "passive"))
    )
    (net (code "74") (name "unconnected-(LEFT_HEADERS-Pad6)") (class "Default")
      (node (ref "LEFT_HEADERS") (pin "6") (pinfunction "6_6") (pintype "passive"))
    )
    (net (code "75") (name "unconnected-(LEFT_HEADERS-Pad7)") (class "Default")
      (node (ref "LEFT_HEADERS") (pin "7") (pinfunction "7_7") (pintype "passive"))
    )
    (net (code "76") (name "unconnected-(LEFT_HEADERS-Pad8)") (class "Default")
      (node (ref "LEFT_HEADERS") (pin "8") (pinfunction "8_8") (pintype "passive"))
    )
    (net (code "77") (name "unconnected-(LEFT_HEADERS-Pad9)") (class "Default")
      (node (ref "LEFT_HEADERS") (pin "9") (pinfunction "9_9") (pintype "passive"))
    )
    (net (code "78") (name "unconnected-(LEFT_HEADERS-Pad10)") (class "Default")
      (node (ref "LEFT_HEADERS") (pin "10") (pinfunction "10_10") (pintype "passive"))
    )
    (net (code "79") (name "unconnected-(LEFT_HEADERS-Pad11)") (class "Default")
      (node (ref "LEFT_HEADERS") (pin "11") (pinfunction "11_11") (pintype "passive"))
    )
    (net (code "80") (name "unconnected-(LEFT_HEADERS-Pad12)") (class "Default")
      (node (ref "LEFT_HEADERS") (pin "12") (pinfunction "12_12") (pintype "passive"))
    )
    (net (code "81") (name "unconnected-(LEFT_HEADERS-Pad13)") (class "Default")
      (node (ref "LEFT_HEADERS") (pin "13") (pinfunction "13_13") (pintype "passive"))
    )
    (net (code "82") (name "unconnected-(LEFT_HEADERS-Pad14)") (class "Default")
      (node (ref "LEFT_HEADERS") (pin "14") (pinfunction "14_14") (pintype "passive"))
    )
    (net (code "83") (name "unconnected-(LEFT_HEADERS-Pad15)") (class "Default")
      (node (ref "LEFT_HEADERS") (pin "15") (pinfunction "15_15") (pintype "passive"))
    )
    (net (code "84") (name "unconnected-(LEFT_HEADERS-Pad17)") (class "Default")
      (node (ref "LEFT_HEADERS") (pin "17") (pinfunction "17_17") (pintype "passive"))
    )
    (net (code "85") (name "unconnected-(LEFT_HEADERS-Pad18)") (class "Default")
      (node (ref "LEFT_HEADERS") (pin "18") (pinfunction "18_18") (pintype "passive"))
    )
    (net (code "86") (name "unconnected-(LEFT_HEADERS-Pad21)") (class "Default")
      (node (ref "LEFT_HEADERS") (pin "21") (pinfunction "21_21") (pintype "passive"))
    )
    (net (code "87") (name "unconnected-(LEFT_HEADERS-Pad23)") (class "Default")
      (node (ref "LEFT_HEADERS") (pin "23") (pinfunction "23_23") (pintype "passive"))
    )
    (net (code "88") (name "unconnected-(LEFT_HEADERS-Pad24)") (class "Default")
      (node (ref "LEFT_HEADERS") (pin "24") (pinfunction "24_24") (pintype "passive"))
    )
    (net (code "89") (name "unconnected-(LEFT_HEADERS-Pad25)") (class "Default")
      (node (ref "LEFT_HEADERS") (pin "25") (pinfunction "25_25") (pintype "passive"))
    )
    (net (code "90") (name "unconnected-(LEFT_HEADERS-Pad26)") (class "Default")
      (node (ref "LEFT_HEADERS") (pin "26") (pinfunction "26_26") (pintype "passive"))
    )
    (net (code "91") (name "unconnected-(LEFT_HEADERS-Pad27)") (class "Default")
      (node (ref "LEFT_HEADERS") (pin "27") (pinfunction "27_27") (pintype "passive"))
    )
    (net (code "92") (name "unconnected-(LEFT_HEADERS-Pad29)") (class "Default")
      (node (ref "LEFT_HEADERS") (pin "29") (pinfunction "29_29") (pintype "passive"))
    )
    (net (code "93") (name "unconnected-(LEFT_HEADERS-Pad31)") (class "Default")
      (node (ref "LEFT_HEADERS") (pin "31") (pinfunction "31_31") (pintype "passive"))
    )
    (net (code "94") (name "unconnected-(LEFT_HEADERS-Pad32)") (class "Default")
      (node (ref "LEFT_HEADERS") (pin "32") (pinfunction "32_32") (pintype "passive"))
    )
    (net (code "95") (name "unconnected-(LEFT_HEADERS-Pad33)") (class "Default")
      (node (ref "LEFT_HEADERS") (pin "33") (pinfunction "33_33") (pintype "passive"))
    )
    (net (code "96") (name "unconnected-(LEFT_HEADERS-Pad35)") (class "Default")
      (node (ref "LEFT_HEADERS") (pin "35") (pinfunction "35_35") (pintype "passive"))
    )
    (net (code "97") (name "unconnected-(LEFT_HEADERS-Pad37)") (class "Default")
      (node (ref "LEFT_HEADERS") (pin "37") (pinfunction "37_37") (pintype "passive"))
    )
    (net (code "98") (name "unconnected-(RIGHT_HEADERS-Pad1)") (class "Default")
      (node (ref "RIGHT_HEADERS") (pin "1") (pinfunction "1_1") (pintype "passive"))
    )
    (net (code "99") (name "unconnected-(RIGHT_HEADERS-Pad2)") (class "Default")
      (node (ref "RIGHT_HEADERS") (pin "2") (pinfunction "2_2") (pintype "passive"))
    )
    (net (code "100") (name "unconnected-(RIGHT_HEADERS-Pad3)") (class "Default")
      (node (ref "RIGHT_HEADERS") (pin "3") (pinfunction "3_3") (pintype "passive"))
    )
    (net (code "101") (name "unconnected-(RIGHT_HEADERS-Pad4)") (class "Default")
      (node (ref "RIGHT_HEADERS") (pin "4") (pinfunction "4_4") (pintype "passive"))
    )
    (net (code "102") (name "unconnected-(RIGHT_HEADERS-Pad5)") (class "Default")
      (node (ref "RIGHT_HEADERS") (pin "5") (pinfunction "5_5") (pintype "passive"))
    )
    (net (code "103") (name "unconnected-(RIGHT_HEADERS-Pad6)") (class "Default")
      (node (ref "RIGHT_HEADERS") (pin "6") (pinfunction "6_6") (pintype "passive"))
    )
    (net (code "104") (name "unconnected-(RIGHT_HEADERS-Pad7)") (class "Default")
      (node (ref "RIGHT_HEADERS") (pin "7") (pinfunction "7_7") (pintype "passive"))
    )
    (net (code "105") (name "unconnected-(RIGHT_HEADERS-Pad8)") (class "Default")
      (node (ref "RIGHT_HEADERS") (pin "8") (pinfunction "8_8") (pintype "passive"))
    )
    (net (code "106") (name "unconnected-(RIGHT_HEADERS-Pad10)") (class "Default")
      (node (ref "RIGHT_HEADERS") (pin "10") (pinfunction "10_10") (pintype "passive"))
    )
    (net (code "107") (name "unconnected-(RIGHT_HEADERS-Pad11)") (class "Default")
      (node (ref "RIGHT_HEADERS") (pin "11") (pinfunction "11_11") (pintype "passive"))
    )
    (net (code "108") (name "unconnected-(RIGHT_HEADERS-Pad12)") (class "Default")
      (node (ref "RIGHT_HEADERS") (pin "12") (pinfunction "12_12") (pintype "passive"))
    )
    (net (code "109") (name "unconnected-(RIGHT_HEADERS-Pad16)") (class "Default")
      (node (ref "RIGHT_HEADERS") (pin "16") (pinfunction "16_16") (pintype "passive"))
    )
    (net (code "110") (name "unconnected-(RIGHT_HEADERS-Pad17)") (class "Default")
      (node (ref "RIGHT_HEADERS") (pin "17") (pinfunction "17_17") (pintype "passive"))
    )
    (net (code "111") (name "unconnected-(RIGHT_HEADERS-Pad18)") (class "Default")
      (node (ref "RIGHT_HEADERS") (pin "18") (pinfunction "18_18") (pintype "passive"))
    )
    (net (code "112") (name "unconnected-(RIGHT_HEADERS-Pad19)") (class "Default")
      (node (ref "RIGHT_HEADERS") (pin "19") (pinfunction "19_19") (pintype "passive"))
    )
    (net (code "113") (name "unconnected-(RIGHT_HEADERS-Pad21)") (class "Default")
      (node (ref "RIGHT_HEADERS") (pin "21") (pinfunction "21_21") (pintype "passive"))
    )
    (net (code "114") (name "unconnected-(RIGHT_HEADERS-Pad22)") (class "Default")
      (node (ref "RIGHT_HEADERS") (pin "22") (pinfunction "22_22") (pintype "passive"))
    )
    (net (code "115") (name "unconnected-(RIGHT_HEADERS-Pad23)") (class "Default")
      (node (ref "RIGHT_HEADERS") (pin "23") (pinfunction "23_23") (pintype "passive"))
    )
    (net (code "116") (name "unconnected-(RIGHT_HEADERS-Pad24)") (class "Default")
      (node (ref "RIGHT_HEADERS") (pin "24") (pinfunction "24_24") (pintype "passive"))
    )
    (net (code "117") (name "unconnected-(RIGHT_HEADERS-Pad25)") (class "Default")
      (node (ref "RIGHT_HEADERS") (pin "25") (pinfunction "25_25") (pintype "passive"))
    )
    (net (code "118") (name "unconnected-(RIGHT_HEADERS-Pad26)") (class "Default")
      (node (ref "RIGHT_HEADERS") (pin "26") (pinfunction "26_26") (pintype "passive"))
    )
    (net (code "119") (name "unconnected-(RIGHT_HEADERS-Pad27)") (class "Default")
      (node (ref "RIGHT_HEADERS") (pin "27") (pinfunction "27_27") (pintype "passive"))
    )
    (net (code "120") (name "unconnected-(RIGHT_HEADERS-Pad28)") (class "Default")
      (node (ref "RIGHT_HEADERS") (pin "28") (pinfunction "28_28") (pintype "passive"))
    )
    (net (code "121") (name "unconnected-(RIGHT_HEADERS-Pad29)") (class "Default")
      (node (ref "RIGHT_HEADERS") (pin "29") (pinfunction "29_29") (pintype "passive"))
    )
    (net (code "122") (name "unconnected-(RIGHT_HEADERS-Pad30)") (class "Default")
      (node (ref "RIGHT_HEADERS") (pin "30") (pinfunction "30_30") (pintype "passive"))
    )
    (net (code "123") (name "unconnected-(RIGHT_HEADERS-Pad31)") (class "Default")
      (node (ref "RIGHT_HEADERS") (pin "31") (pinfunction "31_31") (pintype "passive"))
    )
    (net (code "124") (name "unconnected-(RIGHT_HEADERS-Pad32)") (class "Default")
      (node (ref "RIGHT_HEADERS") (pin "32") (pinfunction "32_32") (pintype "passive"))
    )
    (net (code "125") (name "unconnected-(RIGHT_HEADERS-Pad33)") (class "Default")
      (node (ref "RIGHT_HEADERS") (pin "33") (pinfunction "33_33") (pintype "passive"))
    )
    (net (code "126") (name "unconnected-(RIGHT_HEADERS-Pad34)") (class "Default")
      (node (ref "RIGHT_HEADERS") (pin "34") (pinfunction "34_34") (pintype "passive"))
    )
    (net (code "127") (name "unconnected-(RIGHT_HEADERS-Pad36)") (class "Default")
      (node (ref "RIGHT_HEADERS") (pin "36") (pinfunction "36_36") (pintype "passive"))
    )
    (net (code "128") (name "unconnected-(RIGHT_HEADERS-Pad37)") (class "Default")
      (node (ref "RIGHT_HEADERS") (pin "37") (pinfunction "37_37") (pintype "passive"))
    )
    (net (code "129") (name "unconnected-(RIGHT_HEADERS-Pad38)") (class "Default")
      (node (ref "RIGHT_HEADERS") (pin "38") (pinfunction "38_38") (pintype "passive"))
    )
  )
)
